# IC_Sheet1.net
KiCad netlist of a schematic drawn in Altium Designer
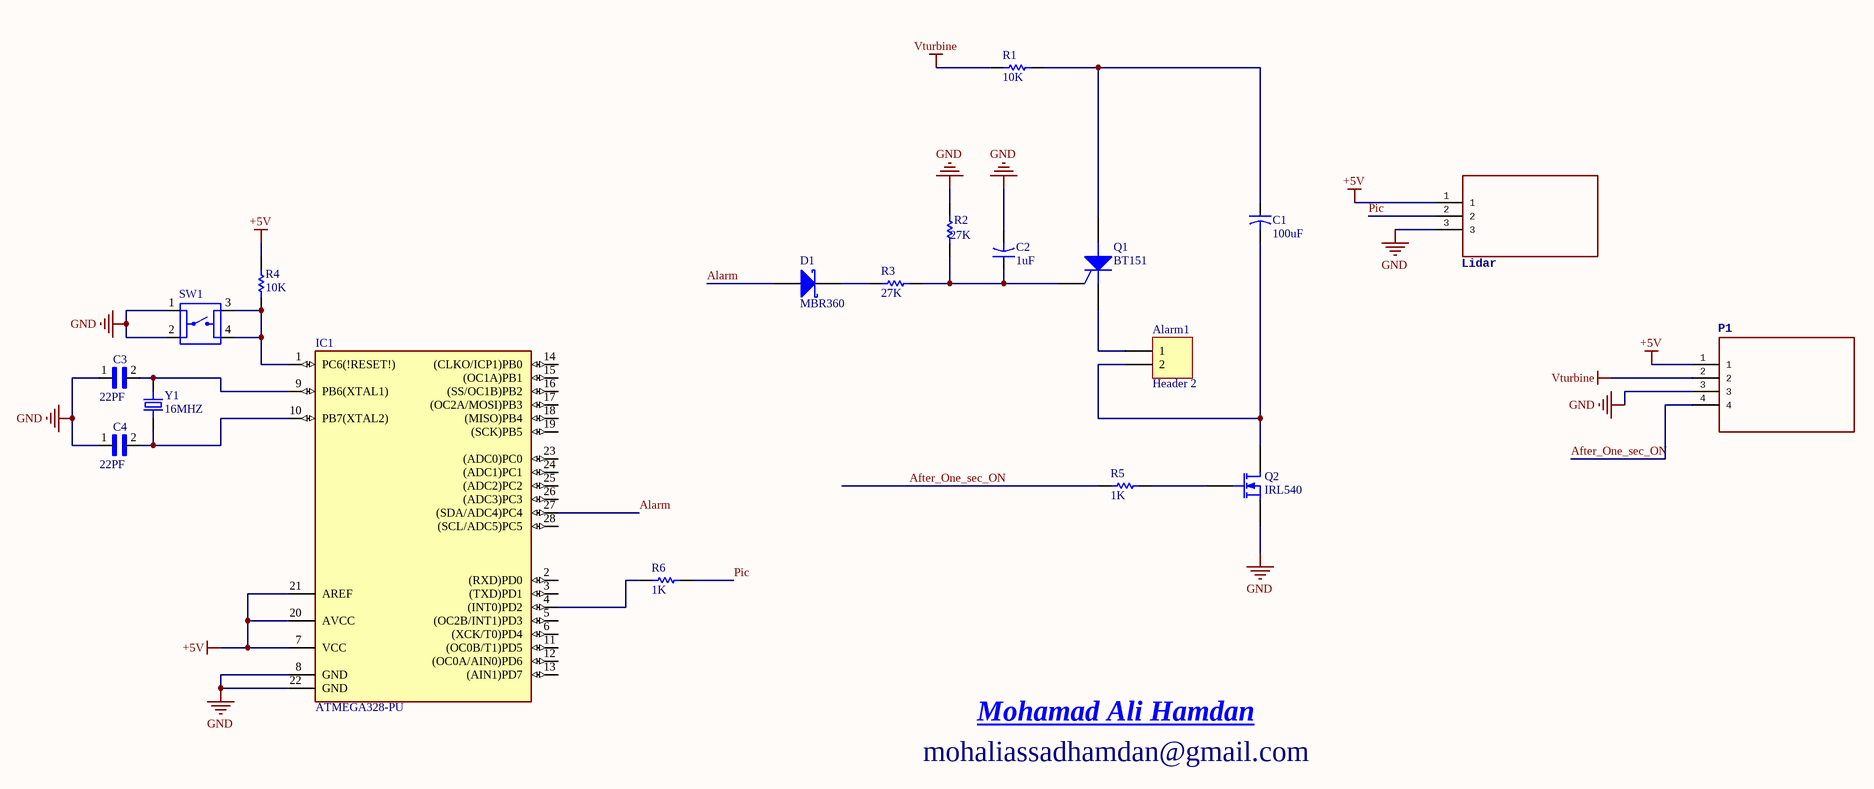
[diagram p0: IC_Sheet1.SchDoc]

(export (version "E")
  (design (tool "Eeschema 10.0.6"))
  (components
    (comp (ref "Alarm1")
      (value "Header 2")
      (footprint "Connector_green_2pins")
      (description "Header, 2-Pin")
      (fields (field (name "PUBLISHER") "Altium Limited"))
      (libsource (lib "Miscellaneous Connectors") (part "Header 2"))
    )
    (comp (ref "C1")
      (value "100uF")
      (footprint "Capacitor_polarized_100uF")
      (description "Capacitor")
      (fields (field (name "Comment") "Cap2") (field (name "PUBLISHER") "Altium Limited"))
      (libsource (lib "Miscellaneous Devices") (part "Cap2"))
    )
    (comp (ref "C2")
      (value "1uF")
      (footprint "Capacitor_polarized_100uF")
      (description "Capacitor")
      (fields (field (name "Comment") "Cap2") (field (name "PUBLISHER") "Altium Limited"))
      (libsource (lib "Miscellaneous Devices") (part "Cap2"))
    )
    (comp (ref "C3")
      (value "14pF")
      (footprint "CAP_RDER71H333K0M1H03A")
      (description "Lead capacitor X7R(EIA) with Capacitance 33000pF, Rated Voltage 50Vdc")
      (fields
        (field (name "MF") "Murata")
        (field (name "MP") "RDER71H333K0M1H03A")
        (field (name "BUYPART") "22PF")
      )
      (libsource (lib "RDER71H333K0M1H03A") (part "RDER71H333K0M1H03A"))
    )
    (comp (ref "C4")
      (value "14pF")
      (footprint "CAP_RDER71H333K0M1H03A")
      (description "Lead capacitor X7R(EIA) with Capacitance 33000pF, Rated Voltage 50Vdc")
      (fields
        (field (name "MF") "Murata")
        (field (name "MP") "RDER71H333K0M1H03A")
        (field (name "BUYPART") "22PF")
      )
      (libsource (lib "RDER71H333K0M1H03A") (part "RDER71H333K0M1H03A"))
    )
    (comp (ref "D1")
      (value "MBR360")
      (footprint "diode 4007")
      (description "Schottky Rectifier")
      (fields (field (name "PUBLISHER") "Altium Limited"))
      (libsource (lib "Miscellaneous Devices") (part "Diode 10TQ035"))
    )
    (comp (ref "IC1")
      (value "ATMEGA328-PU")
      (footprint "Atmega:DIL28")
      (description "AVR AVRÂ® ATmega Microcontroller IC 8-Bit 20MHz 32KB _16K x 16_ FLASH 28-PDIP")
      (fields (field (name "MF") "Microchip Technology"))
      (libsource (lib "Atmega328PU") (part "ATMEGA328-PU"))
    )
    (comp (ref "Lidar")
      (value "SAMTEC-HTSW-103-07-X-SJ")
      (footprint "SAMTEC-HTSW-103-07-X-S")
      (libsource (lib "SAMTEC-HTSW-103-07-X-S") (part "SAMTEC-HTSW-103-07-X-SJ"))
    )
    (comp (ref "P1")
      (value "SAMTEC-HTSW-104-14-X-SJ")
      (footprint "SAMTEC-HTSW-104-14-X-S")
      (libsource (lib "header_4pin_2.54mm") (part "SAMTEC-HTSW-104-14-X-SJ"))
    )
    (comp (ref "Q1")
      (value "BT151")
      (footprint "TO255P1040X460X1975-3")
      (description "Silicon Controlled Rectifier")
      (fields (field (name "PUBLISHER") "Altium Limited"))
      (libsource (lib "Miscellaneous Devices") (part "SCR"))
    )
    (comp (ref "Q2")
      (value "IRL540")
      (footprint "TO254P1054X470X1955-3")
      (description "N-Channel MOSFET")
      (fields (field (name "PUBLISHER") "Altium Limited"))
      (libsource (lib "Miscellaneous Devices") (part "MOSFET-N"))
    )
    (comp (ref "R1")
      (value "10K")
      (footprint "resistor")
      (description "Resistor")
      (fields (field (name "Comment") "Res1") (field (name "PUBLISHER") "Altium Limited"))
      (libsource (lib "Miscellaneous Devices") (part "Res1"))
    )
    (comp (ref "R2")
      (value "27K")
      (footprint "resistor")
      (description "Resistor")
      (fields (field (name "Comment") "Res1") (field (name "PUBLISHER") "Altium Limited"))
      (libsource (lib "Miscellaneous Devices") (part "Res1"))
    )
    (comp (ref "R3")
      (value "27K")
      (footprint "resistor")
      (description "Resistor")
      (fields (field (name "Comment") "Res1") (field (name "PUBLISHER") "Altium Limited"))
      (libsource (lib "Miscellaneous Devices") (part "Res1"))
    )
    (comp (ref "R4")
      (value "10K")
      (footprint "resistor")
      (description "Resistor")
      (fields (field (name "Comment") "Res1") (field (name "PUBLISHER") "Altium Limited"))
      (libsource (lib "Miscellaneous Devices") (part "Res1"))
    )
    (comp (ref "R5")
      (value "1K")
      (footprint "resistor")
      (description "Resistor")
      (fields (field (name "Comment") "Res1") (field (name "PUBLISHER") "Altium Limited"))
      (libsource (lib "Miscellaneous Devices") (part "Res1"))
    )
    (comp (ref "R6")
      (value "1K")
      (footprint "resistor")
      (description "Resistor")
      (fields (field (name "Comment") "Res1") (field (name "PUBLISHER") "Altium Limited"))
      (libsource (lib "Miscellaneous Devices") (part "Res1"))
    )
    (comp (ref "SW1")
      (value "FSM8JH")
      (footprint "SW_FSM8JH")
      (description "Tactile Switch SPST-NO Top Actuated Through Hole")
      (fields (field (name "MF") "TE Connectivity"))
      (libsource (lib "switch") (part "FSM8JH"))
    )
    (comp (ref "Y1")
      (value "16MHZ")
      (footprint "XTAL_ECS-160-20-4VX")
      (description "16MHz Â±30ppm Crystal 20pF 50 Ohms HC-49/US")
      (fields (field (name "MF") "ECS Inc.") (field (name "MP") "ECS-160-20-4VX"))
      (libsource (lib "Crystal") (part "ECS-160-20-4VX"))
    )
  )
  (nets
    (net (code "1") (name "+5V") (class "Default")
      (node (ref "IC1") (pin "20") (pinfunction "AVCC_20") (pintype "power_in"))
      (node (ref "IC1") (pin "21") (pinfunction "AREF_21") (pintype "passive"))
      (node (ref "IC1") (pin "7") (pinfunction "VCC_7") (pintype "power_in"))
      (node (ref "Lidar") (pin "1") (pinfunction "1_1") (pintype "passive"))
      (node (ref "P1") (pin "1") (pinfunction "1_1") (pintype "passive"))
      (node (ref "R4") (pin "2") (pinfunction "2_2") (pintype "passive"))
    )
    (net (code "2") (name "/After_One_sec_ON") (class "Default")
      (node (ref "P1") (pin "4") (pinfunction "4_4") (pintype "passive"))
      (node (ref "R5") (pin "2") (pinfunction "2_2") (pintype "passive"))
    )
    (net (code "3") (name "/Alarm") (class "Default")
      (node (ref "D1") (pin "3") (pinfunction "A_3") (pintype "passive"))
      (node (ref "IC1") (pin "27") (pinfunction "(SDA/ADC4)PC4_27") (pintype "bidirectional"))
    )
    (net (code "4") (name "/Pic") (class "Default")
      (node (ref "Lidar") (pin "2") (pinfunction "2_2") (pintype "passive"))
      (node (ref "R6") (pin "1") (pinfunction "1_1") (pintype "passive"))
    )
    (net (code "5") (name "GND") (class "Default")
      (node (ref "C2") (pin "2") (pinfunction "2_2") (pintype "passive"))
      (node (ref "C3") (pin "1") (pinfunction "1_1") (pintype "passive"))
      (node (ref "C4") (pin "1") (pinfunction "1_1") (pintype "passive"))
      (node (ref "IC1") (pin "22") (pinfunction "GND_22") (pintype "power_in"))
      (node (ref "IC1") (pin "8") (pinfunction "GND_8") (pintype "power_in"))
      (node (ref "Lidar") (pin "3") (pinfunction "3_3") (pintype "passive"))
      (node (ref "P1") (pin "3") (pinfunction "3_3") (pintype "passive"))
      (node (ref "Q2") (pin "3") (pinfunction "S_3") (pintype "passive"))
      (node (ref "R2") (pin "2") (pinfunction "2_2") (pintype "passive"))
      (node (ref "SW1") (pin "1") (pinfunction "1_1") (pintype "passive"))
      (node (ref "SW1") (pin "2") (pinfunction "2_2") (pintype "passive"))
    )
    (net (code "6") (name "Net-(D1-K)") (class "Default")
      (node (ref "D1") (pin "1") (pinfunction "K_1") (pintype "passive"))
      (node (ref "R3") (pin "2") (pinfunction "2_2") (pintype "passive"))
    )
    (net (code "7") (name "Net-(IC1-(INT0)PD2)") (class "Default")
      (node (ref "IC1") (pin "4") (pinfunction "(INT0)PD2_4") (pintype "bidirectional"))
      (node (ref "R6") (pin "2") (pinfunction "2_2") (pintype "passive"))
    )
    (net (code "8") (name "Net-(IC1-PB6(XTAL1))") (class "Default")
      (node (ref "C3") (pin "2") (pinfunction "2_2") (pintype "passive"))
      (node (ref "IC1") (pin "9") (pinfunction "PB6(XTAL1)_9") (pintype "bidirectional"))
      (node (ref "Y1") (pin "2") (pinfunction "2_2") (pintype "passive"))
    )
    (net (code "9") (name "Net-(IC1-PB7(XTAL2))") (class "Default")
      (node (ref "C4") (pin "2") (pinfunction "2_2") (pintype "passive"))
      (node (ref "IC1") (pin "10") (pinfunction "PB7(XTAL2)_10") (pintype "bidirectional"))
      (node (ref "Y1") (pin "1") (pinfunction "1_1") (pintype "passive"))
    )
    (net (code "10") (name "Net-(IC1-PC6(!RESET!))") (class "Default")
      (node (ref "IC1") (pin "1") (pinfunction "PC6(!RESET!)_1") (pintype "bidirectional"))
      (node (ref "R4") (pin "1") (pinfunction "1_1") (pintype "passive"))
      (node (ref "SW1") (pin "3") (pinfunction "3_3") (pintype "passive"))
      (node (ref "SW1") (pin "4") (pinfunction "4_4") (pintype "passive"))
    )
    (net (code "11") (name "Net-(Q1-A)") (class "Default")
      (node (ref "C1") (pin "1") (pinfunction "1_1") (pintype "passive"))
      (node (ref "Q1") (pin "1") (pinfunction "A_1") (pintype "passive"))
      (node (ref "R1") (pin "1") (pinfunction "1_1") (pintype "passive"))
    )
    (net (code "12") (name "Net-(Q1-G)") (class "Default")
      (node (ref "C2") (pin "1") (pinfunction "1_1") (pintype "passive"))
      (node (ref "Q1") (pin "2") (pinfunction "G_2") (pintype "passive"))
      (node (ref "R2") (pin "1") (pinfunction "1_1") (pintype "passive"))
      (node (ref "R3") (pin "1") (pinfunction "1_1") (pintype "passive"))
    )
    (net (code "13") (name "Net-(Q1-K)") (class "Default")
      (node (ref "Alarm1") (pin "1") (pinfunction "1_1") (pintype "passive"))
      (node (ref "Q1") (pin "3") (pinfunction "K_3") (pintype "passive"))
    )
    (net (code "14") (name "Net-(Q2-D)") (class "Default")
      (node (ref "Alarm1") (pin "2") (pinfunction "2_2") (pintype "passive"))
      (node (ref "C1") (pin "2") (pinfunction "2_2") (pintype "passive"))
      (node (ref "Q2") (pin "1") (pinfunction "D_1") (pintype "passive"))
    )
    (net (code "15") (name "Net-(Q2-G)") (class "Default")
      (node (ref "Q2") (pin "2") (pinfunction "G_2") (pintype "passive"))
      (node (ref "R5") (pin "1") (pinfunction "1_1") (pintype "passive"))
    )
    (net (code "16") (name "Vturbine") (class "Default")
      (node (ref "P1") (pin "2") (pinfunction "2_2") (pintype "passive"))
      (node (ref "R1") (pin "2") (pinfunction "2_2") (pintype "passive"))
    )
    (net (code "17") (name "unconnected-(IC1-(ADC0)PC0-Pad23)") (class "Default")
      (node (ref "IC1") (pin "23") (pinfunction "(ADC0)PC0_23") (pintype "bidirectional"))
    )
    (net (code "18") (name "unconnected-(IC1-(ADC1)PC1-Pad24)") (class "Default")
      (node (ref "IC1") (pin "24") (pinfunction "(ADC1)PC1_24") (pintype "bidirectional"))
    )
    (net (code "19") (name "unconnected-(IC1-(ADC2)PC2-Pad25)") (class "Default")
      (node (ref "IC1") (pin "25") (pinfunction "(ADC2)PC2_25") (pintype "bidirectional"))
    )
    (net (code "20") (name "unconnected-(IC1-(ADC3)PC3-Pad26)") (class "Default")
      (node (ref "IC1") (pin "26") (pinfunction "(ADC3)PC3_26") (pintype "bidirectional"))
    )
    (net (code "21") (name "unconnected-(IC1-(AIN1)PD7-Pad13)") (class "Default")
      (node (ref "IC1") (pin "13") (pinfunction "(AIN1)PD7_13") (pintype "bidirectional"))
    )
    (net (code "22") (name "unconnected-(IC1-(CLKO{slash}ICP1)PB0-Pad14)") (class "Default")
      (node (ref "IC1") (pin "14") (pinfunction "(CLKO/ICP1)PB0_14") (pintype "bidirectional"))
    )
    (net (code "23") (name "unconnected-(IC1-(MISO)PB4-Pad18)") (class "Default")
      (node (ref "IC1") (pin "18") (pinfunction "(MISO)PB4_18") (pintype "bidirectional"))
    )
    (net (code "24") (name "unconnected-(IC1-(OC0A{slash}AIN0)PD6-Pad12)") (class "Default")
      (node (ref "IC1") (pin "12") (pinfunction "(OC0A/AIN0)PD6_12") (pintype "bidirectional"))
    )
    (net (code "25") (name "unconnected-(IC1-(OC0B{slash}T1)PD5-Pad11)") (class "Default")
      (node (ref "IC1") (pin "11") (pinfunction "(OC0B/T1)PD5_11") (pintype "bidirectional"))
    )
    (net (code "26") (name "unconnected-(IC1-(OC1A)PB1-Pad15)") (class "Default")
      (node (ref "IC1") (pin "15") (pinfunction "(OC1A)PB1_15") (pintype "bidirectional"))
    )
    (net (code "27") (name "unconnected-(IC1-(OC2A{slash}MOSI)PB3-Pad17)") (class "Default")
      (node (ref "IC1") (pin "17") (pinfunction "(OC2A/MOSI)PB3_17") (pintype "bidirectional"))
    )
    (net (code "28") (name "unconnected-(IC1-(OC2B{slash}INT1)PD3-Pad5)") (class "Default")
      (node (ref "IC1") (pin "5") (pinfunction "(OC2B/INT1)PD3_5") (pintype "bidirectional"))
    )
    (net (code "29") (name "unconnected-(IC1-(RXD)PD0-Pad2)") (class "Default")
      (node (ref "IC1") (pin "2") (pinfunction "(RXD)PD0_2") (pintype "bidirectional"))
    )
    (net (code "30") (name "unconnected-(IC1-(SCK)PB5-Pad19)") (class "Default")
      (node (ref "IC1") (pin "19") (pinfunction "(SCK)PB5_19") (pintype "bidirectional"))
    )
    (net (code "31") (name "unconnected-(IC1-(SCL{slash}ADC5)PC5-Pad28)") (class "Default")
      (node (ref "IC1") (pin "28") (pinfunction "(SCL/ADC5)PC5_28") (pintype "bidirectional"))
    )
    (net (code "32") (name "unconnected-(IC1-(SS{slash}OC1B)PB2-Pad16)") (class "Default")
      (node (ref "IC1") (pin "16") (pinfunction "(SS/OC1B)PB2_16") (pintype "bidirectional"))
    )
    (net (code "33") (name "unconnected-(IC1-(TXD)PD1-Pad3)") (class "Default")
      (node (ref "IC1") (pin "3") (pinfunction "(TXD)PD1_3") (pintype "bidirectional"))
    )
    (net (code "34") (name "unconnected-(IC1-(XCK{slash}T0)PD4-Pad6)") (class "Default")
      (node (ref "IC1") (pin "6") (pinfunction "(XCK/T0)PD4_6") (pintype "bidirectional"))
    )
  )
)
